# obc-v2_CM4-M2.net
KiCad netlist of a schematic drawn in Altium Designer
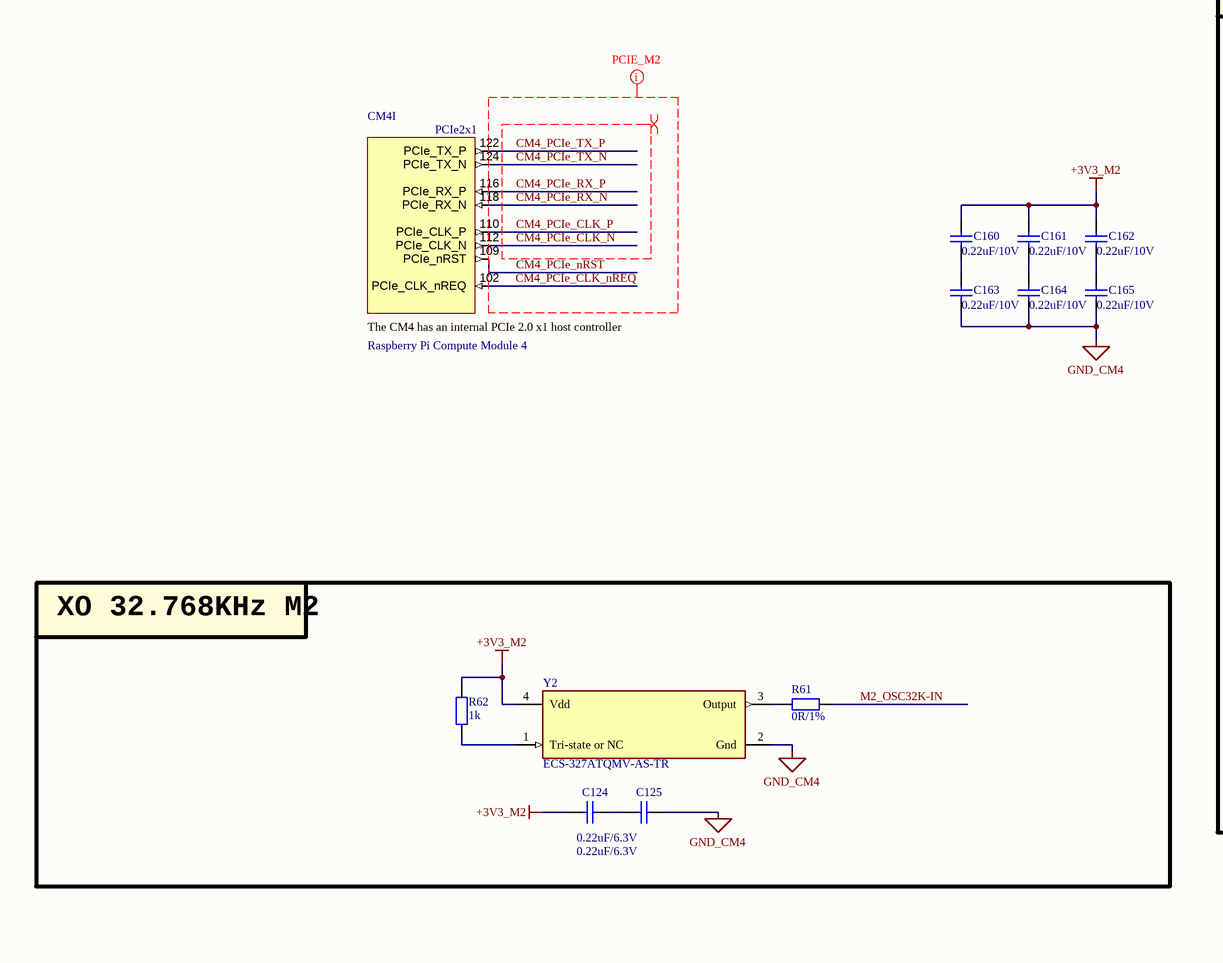
[diagram p0: obc-v2_CM4-M2.SchDoc, left]
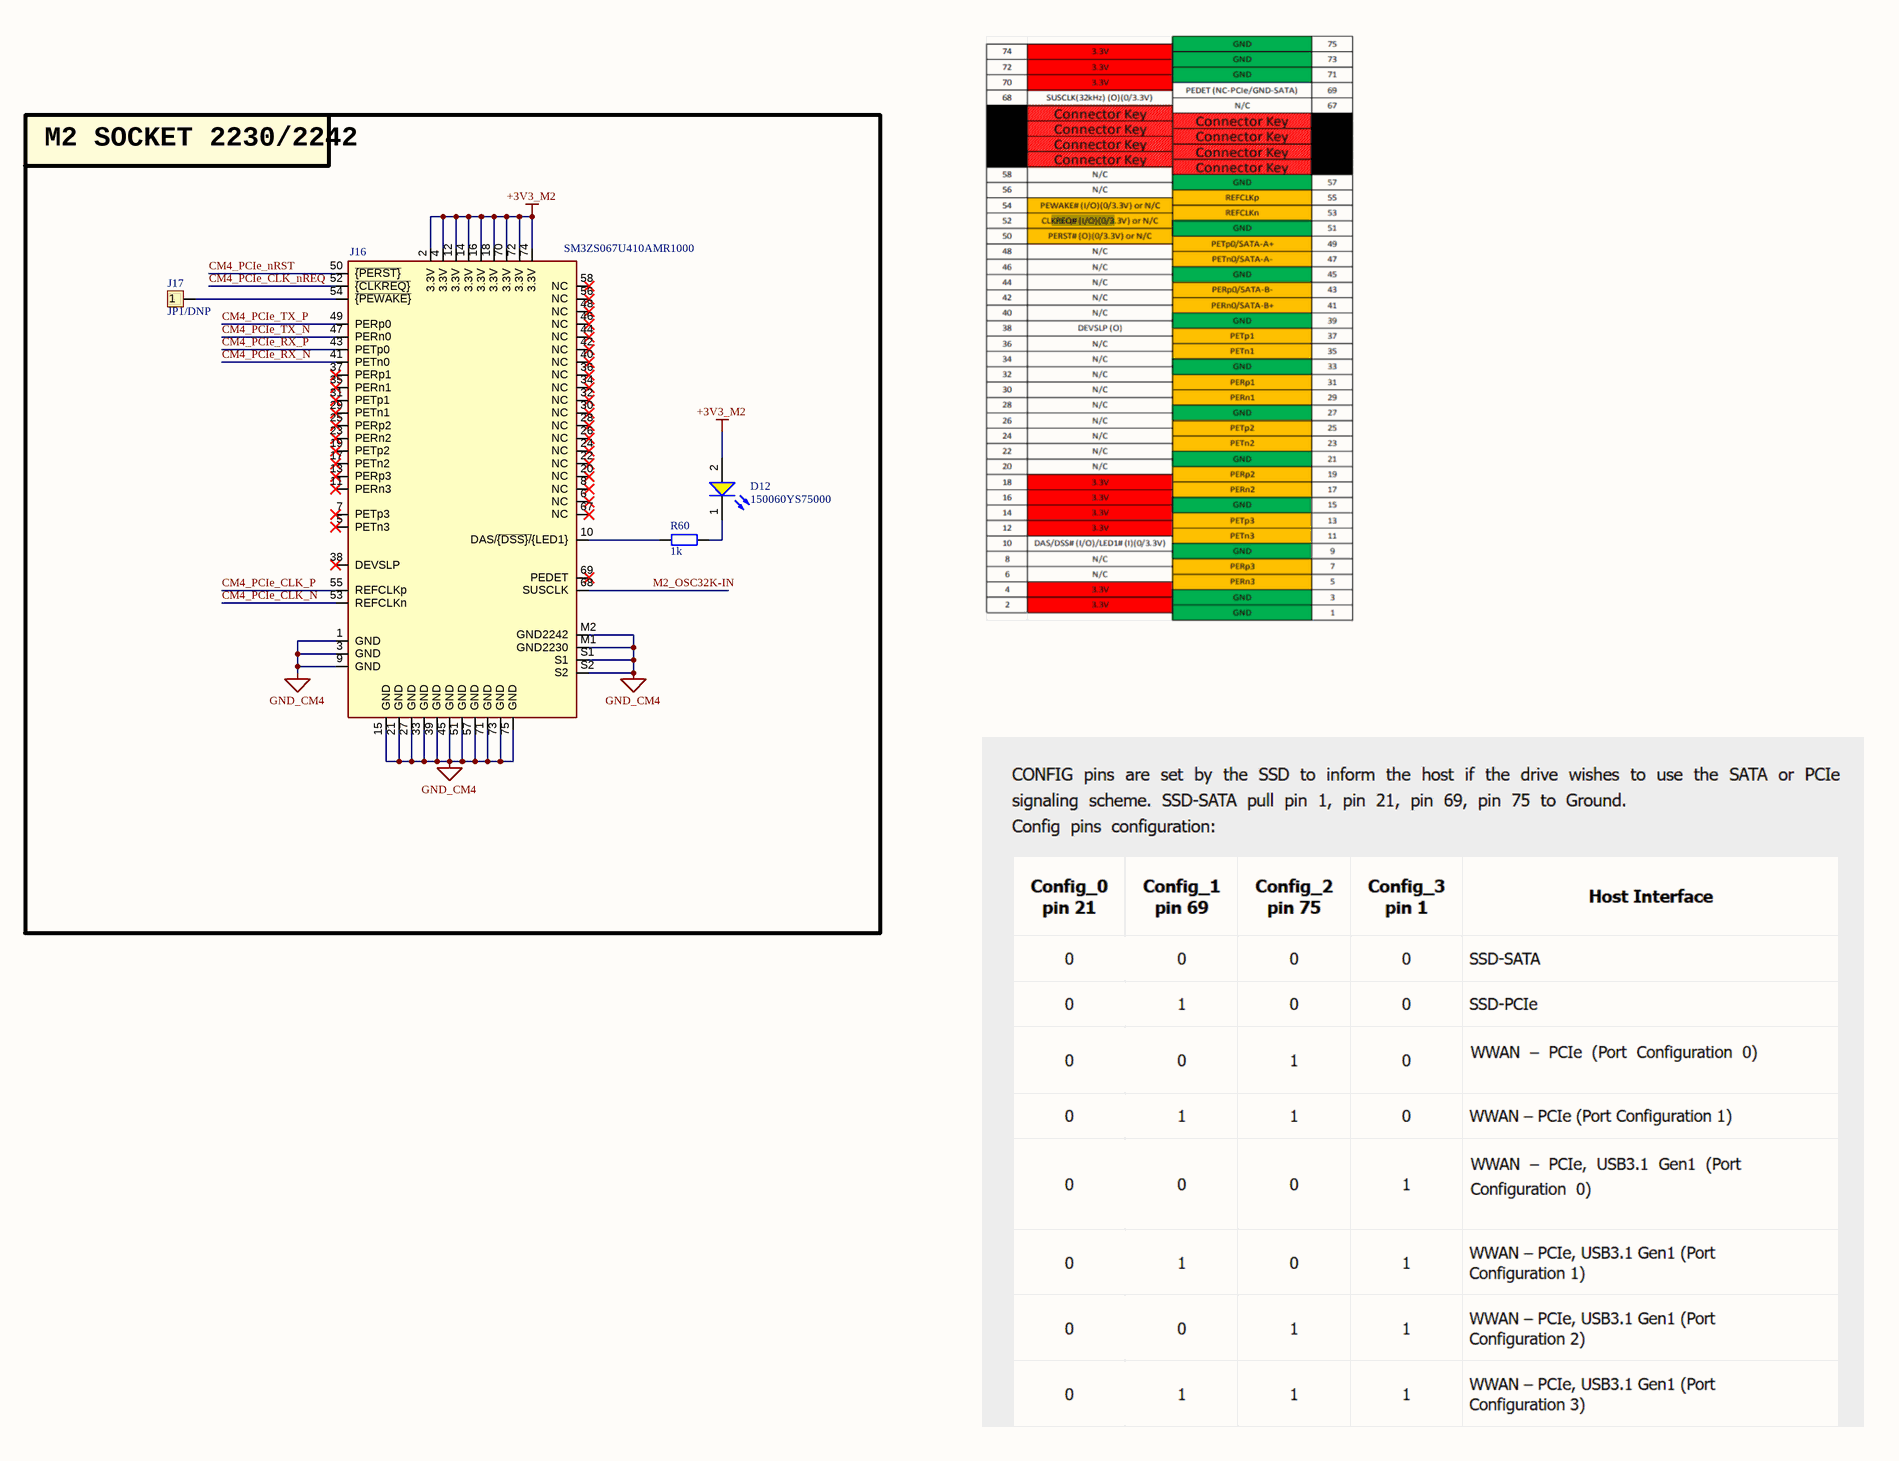
[diagram p1: obc-v2_CM4-M2.SchDoc, right]

(export (version "E")
  (design (tool "Eeschema 10.0.6"))
  (components
    (comp (ref "C124")
      (value "0.22uF/6.3V")
      (footprint "CAP_C_1005X60")
      (description "CAPC")
      (libsource (lib "Altium_Lib_by_KhueNguyenCreator") (part "Tu 0402 33nF 10V"))
    )
    (comp (ref "C125")
      (value "0.22uF/6.3V")
      (footprint "CAP_C_1005X60")
      (description "CAPC")
      (libsource (lib "Altium_Lib_by_KhueNguyenCreator") (part "Tu 0402 33nF 10V"))
    )
    (comp (ref "C160")
      (value "0.22uF/10V")
      (footprint "CAP_C_1005X60")
      (description "CAPC")
      (libsource (lib "Altium_Lib_by_KhueNguyenCreator") (part "Tu 0402 33nF 10V"))
    )
    (comp (ref "C161")
      (value "0.22uF/10V")
      (footprint "CAP_C_1005X60")
      (description "CAPC")
      (libsource (lib "Altium_Lib_by_KhueNguyenCreator") (part "Tu 0402 33nF 10V"))
    )
    (comp (ref "C162")
      (value "0.22uF/10V")
      (footprint "CAP_C_1005X60")
      (description "CAPC")
      (libsource (lib "Altium_Lib_by_KhueNguyenCreator") (part "Tu 0402 33nF 10V"))
    )
    (comp (ref "C163")
      (value "0.22uF/10V")
      (footprint "CAP_C_1005X60")
      (description "CAPC")
      (libsource (lib "Altium_Lib_by_KhueNguyenCreator") (part "Tu 0402 33nF 10V"))
    )
    (comp (ref "C164")
      (value "0.22uF/10V")
      (footprint "CAP_C_1005X60")
      (description "CAPC")
      (libsource (lib "Altium_Lib_by_KhueNguyenCreator") (part "Tu 0402 33nF 10V"))
    )
    (comp (ref "C165")
      (value "0.22uF/10V")
      (footprint "CAP_C_1005X60")
      (description "CAPC")
      (libsource (lib "Altium_Lib_by_KhueNguyenCreator") (part "Tu 0402 33nF 10V"))
    )
    (comp (ref "CM4")
      (value "Raspberry Pi Compute Module 4")
      (footprint "CM4-DF40HC(3.0)-100DS-0.4v_3mm_1.5mm")
      (description "Raspberry Pi Compute Module 4 by Amornthep Phunsin")
      (libsource (lib "CM4") (part "CM4"))
    )
    (comp (ref "D12")
      (value "150060YS75000")
      (footprint "WL-SMCW_0603_150060xx75000")
      (description "LED YELLOW CLEAR 0603 SMD")
      (libsource (lib "Altium Content Vault") (part "LED_Yellow_2A-1K"))
    )
    (comp (ref "J16")
      (value "SM3ZS067U410AMR1000")
      (footprint "M.2 M Key socket")
      (fields (field (name "Comment") "Bus_M.2_Socket_M"))
      (libsource (lib "CM5_GPIO") (part "Bus_M.2_Socket_M"))
    )
    (comp (ref "J17")
      (value "JP1/DNP")
      (footprint "JP1-D1T")
      (description "WR-PHD 2.54 mm Angled Socket Header")
      (fields
        (field (name "MANUFACTURER") "Würth Elektronik eiSos GmbH")
        (field (name "PARTNO") "613002143121")
        (field (name "CREATED BY") "Karrer Zheng")
      )
      (libsource (lib "TechMT.VN_Lib_Project v2") (part "JP1"))
    )
    (comp (ref "R60")
      (value "1k")
      (footprint "RES_C_1608X60")
      (description "RES")
      (libsource (lib "Altium_Lib_by_KhueNguyenCreator") (part "Tro 0603 1% 10k"))
    )
    (comp (ref "R61")
      (value "0R/1%")
      (footprint "RES_C_1608X60")
      (description "RES")
      (libsource (lib "Altium_Lib_by_KhueNguyenCreator") (part "Tro 0603 1% 10k"))
    )
    (comp (ref "R62")
      (value "1k")
      (footprint "RES_C_1608X60")
      (description "RES")
      (libsource (lib "Altium_Lib_by_KhueNguyenCreator") (part "Tro 0603 1% 10k"))
    )
    (comp (ref "Y2")
      (value "ECS-327ATQMV-AS-TR")
      (footprint "FP-327ATQMV-MFG")
      (description "XTAL OSC XO 32.7680KHZ CMOS SMD")
      (libsource (lib "Altium Content Vault") (part "48575ee33648fc99c8f9879a7ebcfb2"))
    )
  )
  (nets
    (net (code "1") (name "+3V3_M2") (class "Default")
      (node (ref "C124") (pin "1") (pinfunction "1_1") (pintype "passive"))
      (node (ref "C160") (pin "1") (pinfunction "1_1") (pintype "passive"))
      (node (ref "C161") (pin "1") (pinfunction "1_1") (pintype "passive"))
      (node (ref "C162") (pin "1") (pinfunction "1_1") (pintype "passive"))
      (node (ref "D12") (pin "2") (pinfunction "A_2") (pintype "passive"))
      (node (ref "J16") (pin "12") (pinfunction "3.3V_12") (pintype "passive"))
      (node (ref "J16") (pin "14") (pinfunction "3.3V_14") (pintype "passive"))
      (node (ref "J16") (pin "16") (pinfunction "3.3V_16") (pintype "passive"))
      (node (ref "J16") (pin "18") (pinfunction "3.3V_18") (pintype "passive"))
      (node (ref "J16") (pin "2") (pinfunction "3.3V_2") (pintype "passive"))
      (node (ref "J16") (pin "4") (pinfunction "3.3V_4") (pintype "passive"))
      (node (ref "J16") (pin "70") (pinfunction "3.3V_70") (pintype "passive"))
      (node (ref "J16") (pin "72") (pinfunction "3.3V_72") (pintype "passive"))
      (node (ref "J16") (pin "74") (pinfunction "3.3V_74") (pintype "passive"))
      (node (ref "R62") (pin "1") (pinfunction "1_1") (pintype "passive"))
      (node (ref "Y2") (pin "4") (pinfunction "Vdd_4") (pintype "power_in"))
    )
    (net (code "2") (name "/CM4_PCIe_CLK_N") (class "Default")
      (node (ref "CM4") (pin "112") (pinfunction "PCIe_CLK_N_112") (pintype "output"))
      (node (ref "J16") (pin "53") (pinfunction "REFCLKn_53") (pintype "passive"))
    )
    (net (code "3") (name "/CM4_PCIe_CLK_P") (class "Default")
      (node (ref "CM4") (pin "110") (pinfunction "PCIe_CLK_P_110") (pintype "output"))
      (node (ref "J16") (pin "55") (pinfunction "REFCLKp_55") (pintype "passive"))
    )
    (net (code "4") (name "/CM4_PCIe_CLK_nREQ") (class "Default")
      (node (ref "CM4") (pin "102") (pinfunction "PCIe_CLK_nREQ_102") (pintype "input"))
      (node (ref "J16") (pin "52") (pinfunction "~{{CLKREQ}}_52") (pintype "passive"))
    )
    (net (code "5") (name "/CM4_PCIe_RX_N") (class "Default")
      (node (ref "CM4") (pin "118") (pinfunction "PCIe_RX_N_118") (pintype "input"))
      (node (ref "J16") (pin "41") (pinfunction "PETn0_41") (pintype "passive"))
    )
    (net (code "6") (name "/CM4_PCIe_RX_P") (class "Default")
      (node (ref "CM4") (pin "116") (pinfunction "PCIe_RX_P_116") (pintype "input"))
      (node (ref "J16") (pin "43") (pinfunction "PETp0_43") (pintype "passive"))
    )
    (net (code "7") (name "/CM4_PCIe_TX_N") (class "Default")
      (node (ref "CM4") (pin "124") (pinfunction "PCIe_TX_N_124") (pintype "output"))
      (node (ref "J16") (pin "47") (pinfunction "PERn0_47") (pintype "passive"))
    )
    (net (code "8") (name "/CM4_PCIe_TX_P") (class "Default")
      (node (ref "CM4") (pin "122") (pinfunction "PCIe_TX_P_122") (pintype "output"))
      (node (ref "J16") (pin "49") (pinfunction "PERp0_49") (pintype "passive"))
    )
    (net (code "9") (name "/CM4_PCIe_nRST") (class "Default")
      (node (ref "CM4") (pin "109") (pinfunction "PCIe_nRST_109") (pintype "output"))
      (node (ref "J16") (pin "50") (pinfunction "~{{PERST}}_50") (pintype "passive"))
    )
    (net (code "10") (name "/M2_OSC32K-IN") (class "Default")
      (node (ref "J16") (pin "68") (pinfunction "SUSCLK_68") (pintype "passive"))
      (node (ref "R61") (pin "1") (pinfunction "1_1") (pintype "passive"))
    )
    (net (code "11") (name "GND_CM4") (class "Default")
      (node (ref "C125") (pin "2") (pinfunction "2_2") (pintype "passive"))
      (node (ref "C163") (pin "2") (pinfunction "2_2") (pintype "passive"))
      (node (ref "C164") (pin "2") (pinfunction "2_2") (pintype "passive"))
      (node (ref "C165") (pin "2") (pinfunction "2_2") (pintype "passive"))
      (node (ref "J16") (pin "1") (pinfunction "GND_1") (pintype "passive"))
      (node (ref "J16") (pin "15") (pinfunction "GND_15") (pintype "passive"))
      (node (ref "J16") (pin "21") (pinfunction "GND_21") (pintype "passive"))
      (node (ref "J16") (pin "27") (pinfunction "GND_27") (pintype "passive"))
      (node (ref "J16") (pin "3") (pinfunction "GND_3") (pintype "passive"))
      (node (ref "J16") (pin "33") (pinfunction "GND_33") (pintype "passive"))
      (node (ref "J16") (pin "39") (pinfunction "GND_39") (pintype "passive"))
      (node (ref "J16") (pin "45") (pinfunction "GND_45") (pintype "passive"))
      (node (ref "J16") (pin "51") (pinfunction "GND_51") (pintype "passive"))
      (node (ref "J16") (pin "57") (pinfunction "GND_57") (pintype "passive"))
      (node (ref "J16") (pin "71") (pinfunction "GND_71") (pintype "passive"))
      (node (ref "J16") (pin "73") (pinfunction "GND_73") (pintype "passive"))
      (node (ref "J16") (pin "75") (pinfunction "GND_75") (pintype "passive"))
      (node (ref "J16") (pin "9") (pinfunction "GND_9") (pintype "passive"))
      (node (ref "J16") (pin "M1") (pinfunction "GND2230_M1") (pintype "passive"))
      (node (ref "J16") (pin "M2") (pinfunction "GND2242_M2") (pintype "passive"))
      (node (ref "J16") (pin "S1") (pinfunction "S1_S1") (pintype "passive"))
      (node (ref "J16") (pin "S2") (pinfunction "S2_S2") (pintype "passive"))
      (node (ref "Y2") (pin "2") (pinfunction "Gnd_2") (pintype "power_in"))
    )
    (net (code "12") (name "Net-(C124-Pad2)") (class "Default")
      (node (ref "C124") (pin "2") (pinfunction "2_2") (pintype "passive"))
      (node (ref "C125") (pin "1") (pinfunction "1_1") (pintype "passive"))
    )
    (net (code "13") (name "Net-(C160-Pad2)") (class "Default")
      (node (ref "C160") (pin "2") (pinfunction "2_2") (pintype "passive"))
      (node (ref "C163") (pin "1") (pinfunction "1_1") (pintype "passive"))
    )
    (net (code "14") (name "Net-(C161-Pad2)") (class "Default")
      (node (ref "C161") (pin "2") (pinfunction "2_2") (pintype "passive"))
      (node (ref "C164") (pin "1") (pinfunction "1_1") (pintype "passive"))
    )
    (net (code "15") (name "Net-(C162-Pad2)") (class "Default")
      (node (ref "C162") (pin "2") (pinfunction "2_2") (pintype "passive"))
      (node (ref "C165") (pin "1") (pinfunction "1_1") (pintype "passive"))
    )
    (net (code "16") (name "Net-(D12-K)") (class "Default")
      (node (ref "D12") (pin "1") (pinfunction "K_1") (pintype "passive"))
      (node (ref "R60") (pin "1") (pinfunction "1_1") (pintype "passive"))
    )
    (net (code "17") (name "Net-(J16-DAS{slash}~{{DSS}{slash}}{LED1})") (class "Default")
      (node (ref "J16") (pin "10") (pinfunction "DAS/~{{DSS}/}{LED1}_10") (pintype "passive"))
      (node (ref "R60") (pin "2") (pinfunction "2_2") (pintype "passive"))
    )
    (net (code "18") (name "Net-(J16-~{{PEWAKE}})") (class "Default")
      (node (ref "J16") (pin "54") (pinfunction "~{{PEWAKE}}_54") (pintype "passive"))
      (node (ref "J17") (pin "1") (pinfunction "1_1") (pintype "passive"))
    )
    (net (code "19") (name "Net-(Y2-Output)") (class "Default")
      (node (ref "R61") (pin "2") (pinfunction "2_2") (pintype "passive"))
      (node (ref "Y2") (pin "3") (pinfunction "Output_3") (pintype "output"))
    )
    (net (code "20") (name "Net-(Y2-Tri-state_or_NC)") (class "Default")
      (node (ref "R62") (pin "2") (pinfunction "2_2") (pintype "passive"))
      (node (ref "Y2") (pin "1") (pinfunction "Tri-state_or_NC_1") (pintype "input"))
    )
    (net (code "21") (name "unconnected-(J16-DEVSLP-Pad38)") (class "Default")
      (node (ref "J16") (pin "38") (pinfunction "DEVSLP_38") (pintype "passive+no_connect"))
    )
    (net (code "22") (name "unconnected-(J16-NC-Pad6)") (class "Default")
      (node (ref "J16") (pin "6") (pinfunction "NC_6") (pintype "passive+no_connect"))
    )
    (net (code "23") (name "unconnected-(J16-NC-Pad8)") (class "Default")
      (node (ref "J16") (pin "8") (pinfunction "NC_8") (pintype "passive+no_connect"))
    )
    (net (code "24") (name "unconnected-(J16-NC-Pad20)") (class "Default")
      (node (ref "J16") (pin "20") (pinfunction "NC_20") (pintype "passive+no_connect"))
    )
    (net (code "25") (name "unconnected-(J16-NC-Pad22)") (class "Default")
      (node (ref "J16") (pin "22") (pinfunction "NC_22") (pintype "passive+no_connect"))
    )
    (net (code "26") (name "unconnected-(J16-NC-Pad24)") (class "Default")
      (node (ref "J16") (pin "24") (pinfunction "NC_24") (pintype "passive+no_connect"))
    )
    (net (code "27") (name "unconnected-(J16-NC-Pad26)") (class "Default")
      (node (ref "J16") (pin "26") (pinfunction "NC_26") (pintype "passive+no_connect"))
    )
    (net (code "28") (name "unconnected-(J16-NC-Pad28)") (class "Default")
      (node (ref "J16") (pin "28") (pinfunction "NC_28") (pintype "passive+no_connect"))
    )
    (net (code "29") (name "unconnected-(J16-NC-Pad30)") (class "Default")
      (node (ref "J16") (pin "30") (pinfunction "NC_30") (pintype "passive+no_connect"))
    )
    (net (code "30") (name "unconnected-(J16-NC-Pad32)") (class "Default")
      (node (ref "J16") (pin "32") (pinfunction "NC_32") (pintype "passive+no_connect"))
    )
    (net (code "31") (name "unconnected-(J16-NC-Pad34)") (class "Default")
      (node (ref "J16") (pin "34") (pinfunction "NC_34") (pintype "passive+no_connect"))
    )
    (net (code "32") (name "unconnected-(J16-NC-Pad36)") (class "Default")
      (node (ref "J16") (pin "36") (pinfunction "NC_36") (pintype "passive+no_connect"))
    )
    (net (code "33") (name "unconnected-(J16-NC-Pad40)") (class "Default")
      (node (ref "J16") (pin "40") (pinfunction "NC_40") (pintype "passive+no_connect"))
    )
    (net (code "34") (name "unconnected-(J16-NC-Pad42)") (class "Default")
      (node (ref "J16") (pin "42") (pinfunction "NC_42") (pintype "passive+no_connect"))
    )
    (net (code "35") (name "unconnected-(J16-NC-Pad44)") (class "Default")
      (node (ref "J16") (pin "44") (pinfunction "NC_44") (pintype "passive+no_connect"))
    )
    (net (code "36") (name "unconnected-(J16-NC-Pad46)") (class "Default")
      (node (ref "J16") (pin "46") (pinfunction "NC_46") (pintype "passive+no_connect"))
    )
    (net (code "37") (name "unconnected-(J16-NC-Pad48)") (class "Default")
      (node (ref "J16") (pin "48") (pinfunction "NC_48") (pintype "passive+no_connect"))
    )
    (net (code "38") (name "unconnected-(J16-NC-Pad56)") (class "Default")
      (node (ref "J16") (pin "56") (pinfunction "NC_56") (pintype "passive+no_connect"))
    )
    (net (code "39") (name "unconnected-(J16-NC-Pad58)") (class "Default")
      (node (ref "J16") (pin "58") (pinfunction "NC_58") (pintype "passive+no_connect"))
    )
    (net (code "40") (name "unconnected-(J16-NC-Pad67)") (class "Default")
      (node (ref "J16") (pin "67") (pinfunction "NC_67") (pintype "passive+no_connect"))
    )
    (net (code "41") (name "unconnected-(J16-PEDET-Pad69)") (class "Default")
      (node (ref "J16") (pin "69") (pinfunction "PEDET_69") (pintype "passive+no_connect"))
    )
    (net (code "42") (name "unconnected-(J16-PERn1-Pad35)") (class "Default")
      (node (ref "J16") (pin "35") (pinfunction "PERn1_35") (pintype "passive+no_connect"))
    )
    (net (code "43") (name "unconnected-(J16-PERn2-Pad23)") (class "Default")
      (node (ref "J16") (pin "23") (pinfunction "PERn2_23") (pintype "passive+no_connect"))
    )
    (net (code "44") (name "unconnected-(J16-PERn3-Pad11)") (class "Default")
      (node (ref "J16") (pin "11") (pinfunction "PERn3_11") (pintype "passive+no_connect"))
    )
    (net (code "45") (name "unconnected-(J16-PERp1-Pad37)") (class "Default")
      (node (ref "J16") (pin "37") (pinfunction "PERp1_37") (pintype "passive+no_connect"))
    )
    (net (code "46") (name "unconnected-(J16-PERp2-Pad25)") (class "Default")
      (node (ref "J16") (pin "25") (pinfunction "PERp2_25") (pintype "passive+no_connect"))
    )
    (net (code "47") (name "unconnected-(J16-PERp3-Pad13)") (class "Default")
      (node (ref "J16") (pin "13") (pinfunction "PERp3_13") (pintype "passive+no_connect"))
    )
    (net (code "48") (name "unconnected-(J16-PETn1-Pad29)") (class "Default")
      (node (ref "J16") (pin "29") (pinfunction "PETn1_29") (pintype "passive+no_connect"))
    )
    (net (code "49") (name "unconnected-(J16-PETn2-Pad17)") (class "Default")
      (node (ref "J16") (pin "17") (pinfunction "PETn2_17") (pintype "passive+no_connect"))
    )
    (net (code "50") (name "unconnected-(J16-PETn3-Pad5)") (class "Default")
      (node (ref "J16") (pin "5") (pinfunction "PETn3_5") (pintype "passive+no_connect"))
    )
    (net (code "51") (name "unconnected-(J16-PETp1-Pad31)") (class "Default")
      (node (ref "J16") (pin "31") (pinfunction "PETp1_31") (pintype "passive+no_connect"))
    )
    (net (code "52") (name "unconnected-(J16-PETp2-Pad19)") (class "Default")
      (node (ref "J16") (pin "19") (pinfunction "PETp2_19") (pintype "passive+no_connect"))
    )
    (net (code "53") (name "unconnected-(J16-PETp3-Pad7)") (class "Default")
      (node (ref "J16") (pin "7") (pinfunction "PETp3_7") (pintype "passive+no_connect"))
    )
  )
)
